# Master_Power.net
KiCad netlist of a schematic drawn in Altium Designer
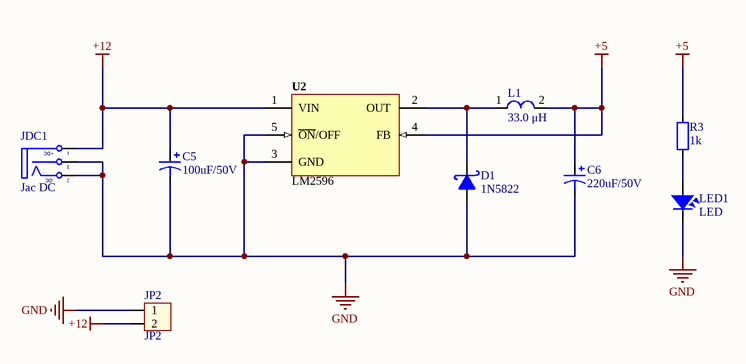
[diagram p0: Master_Power.SchDoc]

(export (version "E")
  (design (tool "Eeschema 10.0.6"))
  (components
    (comp (ref "C5")
      (value "100uF/50V")
      (footprint "C8mm")
      (description "Polarized Capacitor (Axial)")
      (fields (field (name "PUBLISHER") "Altium Limited"))
      (libsource (lib "My Library") (part "Cap Pol"))
    )
    (comp (ref "C6")
      (value "220uF/50V")
      (footprint "C8mm")
      (description "Polarized Capacitor (Axial)")
      (fields (field (name "PUBLISHER") "Altium Limited"))
      (libsource (lib "My Library") (part "Cap Pol"))
    )
    (comp (ref "D1")
      (value "1N5822")
      (footprint "SMA")
      (description "Schottky Rectifiers")
      (libsource (lib "My Library") (part "1N5822"))
    )
    (comp (ref "JDC1")
      (value "Jac DC")
      (footprint "DC-IN")
      (description "Jac DC input")
      (libsource (lib "My Library") (part "DCIN"))
    )
    (comp (ref "JP2")
      (value "JP2")
      (footprint "CON2")
      (description "Connector 2")
      (libsource (lib "My Library") (part "Con2"))
    )
    (comp (ref "L1")
      (value "33.0 μH")
      (footprint "L-SMD-M-7.3x4.5")
      (fields
        (field (name "PARTNO") "78477010")
        (field (name "MANUFACTURER") "Wurth Elektronik")
        (field (name "CREATED BY") "Baojun Chen")
      )
      (libsource (lib "My Library") (part "L-SMD-1"))
    )
    (comp (ref "LED1")
      (value "LED")
      (footprint "LED-0805-Red")
      (description "LED Single colour Green and Red")
      (libsource (lib "My Library") (part "LED"))
    )
    (comp (ref "R3")
      (value "1k")
      (footprint "RES-SMD-0805")
      (description "Resistor")
      (fields
        (field (name "MANUFACTURER") "Generic Components")
        (field (name "PUBLISHER") "Altium Hobart Technology Centre")
      )
      (libsource (lib "My Library") (part "Resistor - SMD"))
    )
    (comp (ref "U2") (value "LM2596") (footprint "TO263-5") (libsource (lib "My Library") (part "LM2596")))
  )
  (nets
    (net (code "1") (name "+5") (class "Default")
      (node (ref "C6") (pin "1") (pinfunction "1_1") (pintype "passive"))
      (node (ref "L1") (pin "2") (pinfunction "2_2") (pintype "passive"))
      (node (ref "R3") (pin "2") (pinfunction "2_2") (pintype "passive"))
      (node (ref "U2") (pin "4") (pinfunction "FB_4") (pintype "input"))
    )
    (net (code "2") (name "+12") (class "Default")
      (node (ref "C5") (pin "1") (pinfunction "1_1") (pintype "passive"))
      (node (ref "JDC1") (pin "1") (pinfunction "T_1") (pintype "passive"))
      (node (ref "JP2") (pin "2") (pinfunction "2_2") (pintype "passive"))
      (node (ref "U2") (pin "1") (pinfunction "VIN_1") (pintype "power_in"))
    )
    (net (code "5") (name "GND") (class "Default")
      (node (ref "C5") (pin "2") (pinfunction "2_2") (pintype "passive"))
      (node (ref "C6") (pin "2") (pinfunction "2_2") (pintype "passive"))
      (node (ref "D1") (pin "1") (pinfunction "A_1") (pintype "passive"))
      (node (ref "JDC1") (pin "2") (pinfunction "TN_2") (pintype "passive"))
      (node (ref "JDC1") (pin "3") (pinfunction "S_3") (pintype "power_in"))
      (node (ref "JP2") (pin "1") (pinfunction "1_1") (pintype "passive"))
      (node (ref "LED1") (pin "2") (pinfunction "2_2") (pintype "passive"))
      (node (ref "U2") (pin "3") (pinfunction "GND_3") (pintype "power_in"))
      (node (ref "U2") (pin "5") (pinfunction "~{ON}/OFF_5") (pintype "input"))
    )
    (net (code "6") (name "Net-(D1-K)") (class "Default")
      (node (ref "D1") (pin "2") (pinfunction "K_2") (pintype "passive"))
      (node (ref "L1") (pin "1") (pinfunction "1_1") (pintype "passive"))
      (node (ref "U2") (pin "2") (pinfunction "OUT_2") (pintype "power_in"))
    )
    (net (code "7") (name "Net-(LED1-Pad1)") (class "Default")
      (node (ref "LED1") (pin "1") (pinfunction "1_1") (pintype "passive"))
      (node (ref "R3") (pin "1") (pinfunction "1_1") (pintype "passive"))
    )
  )
)
